# ControlVoltage.net
KiCad netlist of a schematic drawn in Altium Designer
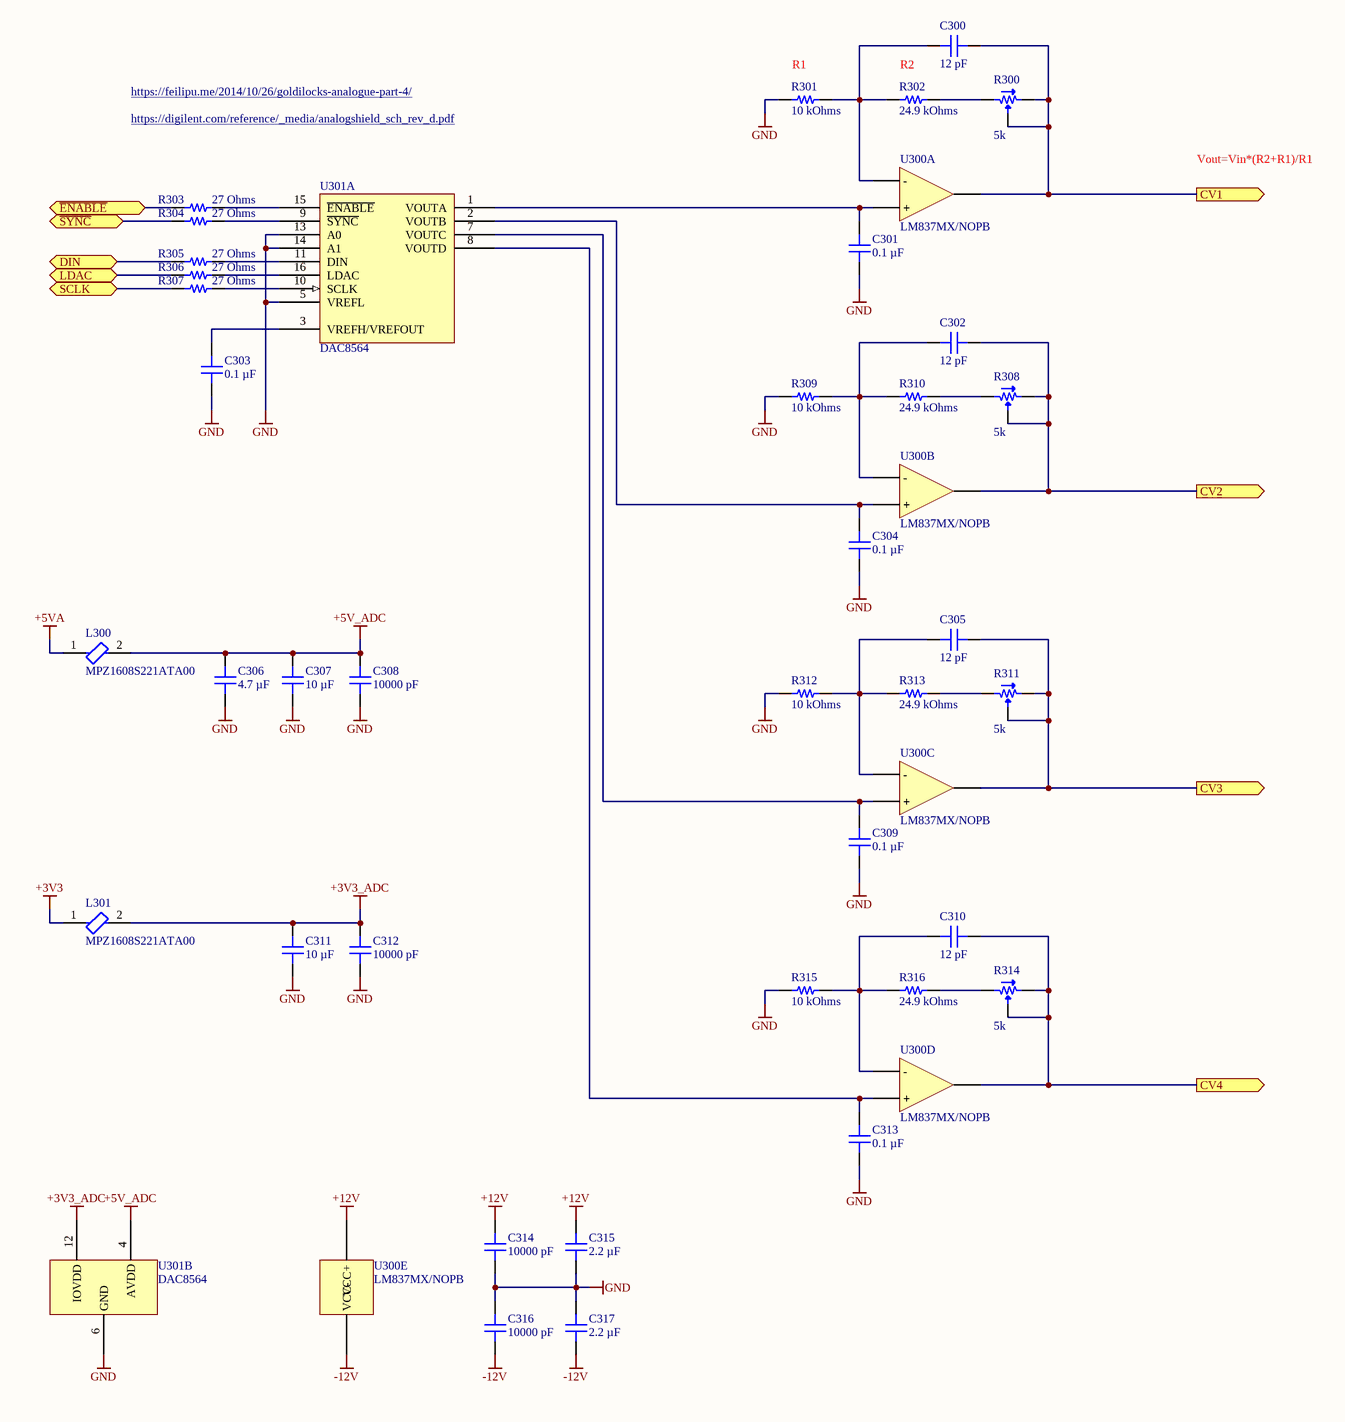
[diagram p0: ControlVoltage.SchDoc]

(export (version "E")
  (design (tool "Eeschema 10.0.6"))
  (components
    (comp (ref "C300")
      (value "12 pF")
      (footprint "CAP 0603_1608")
      (description "CAP CER 12PF 50V C0G/NPO 0603")
      (fields (field (name "PART NUMBER") "CC0603KRNPO9BN120") (field (name "MANUFACTURER") "Yageo"))
      (libsource (lib "Celestial Altium Library") (part "Capacitor"))
    )
    (comp (ref "C301")
      (value "0.1 µF")
      (footprint "CAP 0603_1608")
      (description "CAP CER 0.1UF 16V X7R 0603")
      (fields (field (name "PART NUMBER") "CS0603KRX7R7BB104") (field (name "MANUFACTURER") "Yageo"))
      (libsource (lib "Celestial Altium Library") (part "Capacitor"))
    )
    (comp (ref "C302")
      (value "12 pF")
      (footprint "CAP 0603_1608")
      (description "CAP CER 12PF 50V C0G/NPO 0603")
      (fields (field (name "PART NUMBER") "CC0603KRNPO9BN120") (field (name "MANUFACTURER") "Yageo"))
      (libsource (lib "Celestial Altium Library") (part "Capacitor"))
    )
    (comp (ref "C303")
      (value "0.1 µF")
      (footprint "CAP 0603_1608")
      (description "CAP CER 0.1UF 25V Y5V 0603")
      (fields (field (name "PART NUMBER") "CC0603MRY5V8BB104") (field (name "MANUFACTURER") "Yageo"))
      (libsource (lib "Celestial Altium Library") (part "Capacitor"))
    )
    (comp (ref "C304")
      (value "0.1 µF")
      (footprint "CAP 0603_1608")
      (description "CAP CER 0.1UF 16V X7R 0603")
      (fields (field (name "PART NUMBER") "CS0603KRX7R7BB104") (field (name "MANUFACTURER") "Yageo"))
      (libsource (lib "Celestial Altium Library") (part "Capacitor"))
    )
    (comp (ref "C305")
      (value "12 pF")
      (footprint "CAP 0603_1608")
      (description "CAP CER 12PF 50V C0G/NPO 0603")
      (fields (field (name "PART NUMBER") "CC0603KRNPO9BN120") (field (name "MANUFACTURER") "Yageo"))
      (libsource (lib "Celestial Altium Library") (part "Capacitor"))
    )
    (comp (ref "C306")
      (value "4.7 µF")
      (footprint "CAP 0603_1608")
      (description "CAP CER 4.7UF 10V X5R 0603")
      (fields (field (name "PART NUMBER") "CC0603MRX5R6BB475") (field (name "MANUFACTURER") "Yageo"))
      (libsource (lib "Celestial Altium Library") (part "Capacitor"))
    )
    (comp (ref "C307")
      (value "10 µF")
      (footprint "CAP 0603_1608")
      (description "CAP CER 10UF 4V X5R 0603")
      (fields (field (name "PART NUMBER") "CC0603MRX5R4BB106") (field (name "MANUFACTURER") "Yageo"))
      (libsource (lib "Celestial Altium Library") (part "Capacitor"))
    )
    (comp (ref "C308")
      (value "10000 pF")
      (footprint "CAP 0603_1608")
      (description "CAP CER 10000PF 50V X7R 0603")
      (fields (field (name "PART NUMBER") "CC0603JRX7R9BB103") (field (name "MANUFACTURER") "Yageo"))
      (libsource (lib "Celestial Altium Library") (part "Capacitor"))
    )
    (comp (ref "C309")
      (value "0.1 µF")
      (footprint "CAP 0603_1608")
      (description "CAP CER 0.1UF 16V X7R 0603")
      (fields (field (name "PART NUMBER") "CS0603KRX7R7BB104") (field (name "MANUFACTURER") "Yageo"))
      (libsource (lib "Celestial Altium Library") (part "Capacitor"))
    )
    (comp (ref "C310")
      (value "12 pF")
      (footprint "CAP 0603_1608")
      (description "CAP CER 12PF 50V C0G/NPO 0603")
      (fields (field (name "PART NUMBER") "CC0603KRNPO9BN120") (field (name "MANUFACTURER") "Yageo"))
      (libsource (lib "Celestial Altium Library") (part "Capacitor"))
    )
    (comp (ref "C311")
      (value "10 µF")
      (footprint "CAP 0603_1608")
      (description "CAP CER 10UF 4V X5R 0603")
      (fields (field (name "PART NUMBER") "CC0603MRX5R4BB106") (field (name "MANUFACTURER") "Yageo"))
      (libsource (lib "Celestial Altium Library") (part "Capacitor"))
    )
    (comp (ref "C312")
      (value "10000 pF")
      (footprint "CAP 0603_1608")
      (description "CAP CER 10000PF 50V X7R 0603")
      (fields (field (name "PART NUMBER") "CC0603JRX7R9BB103") (field (name "MANUFACTURER") "Yageo"))
      (libsource (lib "Celestial Altium Library") (part "Capacitor"))
    )
    (comp (ref "C313")
      (value "0.1 µF")
      (footprint "CAP 0603_1608")
      (description "CAP CER 0.1UF 16V X7R 0603")
      (fields (field (name "PART NUMBER") "CS0603KRX7R7BB104") (field (name "MANUFACTURER") "Yageo"))
      (libsource (lib "Celestial Altium Library") (part "Capacitor"))
    )
    (comp (ref "C314")
      (value "10000 pF")
      (footprint "CAP 0603_1608")
      (description "CAP CER 10000PF 50V X7R 0603")
      (fields (field (name "PART NUMBER") "CC0603JRX7R9BB103") (field (name "MANUFACTURER") "Yageo"))
      (libsource (lib "Celestial Altium Library") (part "Capacitor"))
    )
    (comp (ref "C315")
      (value "2.2 µF")
      (footprint "CAP 0603_1608")
      (description "CAP CER 2.2UF 16V Y5V 0603")
      (fields (field (name "PART NUMBER") "CC0603ZRY5V7BB225") (field (name "MANUFACTURER") "Yageo"))
      (libsource (lib "Celestial Altium Library") (part "Capacitor"))
    )
    (comp (ref "C316")
      (value "10000 pF")
      (footprint "CAP 0603_1608")
      (description "CAP CER 10000PF 50V X7R 0603")
      (fields (field (name "PART NUMBER") "CC0603JRX7R9BB103") (field (name "MANUFACTURER") "Yageo"))
      (libsource (lib "Celestial Altium Library") (part "Capacitor"))
    )
    (comp (ref "C317")
      (value "2.2 µF")
      (footprint "CAP 0603_1608")
      (description "CAP CER 2.2UF 16V Y5V 0603")
      (fields (field (name "PART NUMBER") "CC0603ZRY5V7BB225") (field (name "MANUFACTURER") "Yageo"))
      (libsource (lib "Celestial Altium Library") (part "Capacitor"))
    )
    (comp (ref "L300")
      (value "MPZ1608S221ATA00")
      (footprint "FP-MPZ1608-0_8-MFG")
      (description "Power line Ferrite Bead 220Ω @ 100MHz 2.2A DCR 0.05Ω SMD 0603")
      (fields (field (name "TOLERANCE") "25%"))
      (libsource (lib "Altium Content Vault") (part "5f30dd21d616792df468990f7003faa"))
    )
    (comp (ref "L301")
      (value "MPZ1608S221ATA00")
      (footprint "FP-MPZ1608-0_8-MFG")
      (description "Power line Ferrite Bead 220Ω @ 100MHz 2.2A DCR 0.05Ω SMD 0603")
      (fields (field (name "TOLERANCE") "25%"))
      (libsource (lib "Altium Content Vault") (part "5f30dd21d616792df468990f7003faa"))
    )
    (comp (ref "R300")
      (value "5k")
      (footprint "BOURNS_TRIM_3296")
      (description "Bourns Trimmer Resistor - Through Hole - Series 3296")
      (libsource (lib "LabratsSynthLib") (part "BOURNS_TRIM_POT_3296"))
    )
    (comp (ref "R301")
      (value "10 kOhms")
      (footprint "RES 0603_1608")
      (description "RES SMD 10K OHM 1% 1/10W 0603")
      (fields (field (name "PART NUMBER") "CRCW060310K0FKTA") (field (name "MANUFACTURER") "Vishay Dale"))
      (libsource (lib "Celestial Altium Library") (part "Resistor"))
    )
    (comp (ref "R302")
      (value "24.9 kOhms")
      (footprint "RES 0603_1608")
      (description "RES 24.9K OHM 1% 1/10W 0603")
      (fields (field (name "PART NUMBER") "CRCW060324K9FKEAC") (field (name "MANUFACTURER") "Vishay Dale"))
      (libsource (lib "Celestial Altium Library") (part "Resistor"))
    )
    (comp (ref "R303")
      (value "27 Ohms")
      (footprint "RES 0603_1608")
      (description "RES SMD 27 OHM 1% 1/10W 0603")
      (fields (field (name "PART NUMBER") "CRCW060327R0FKEA") (field (name "MANUFACTURER") "Vishay Dale"))
      (libsource (lib "Celestial Altium Library") (part "Resistor"))
    )
    (comp (ref "R304")
      (value "27 Ohms")
      (footprint "RES 0603_1608")
      (description "RES SMD 27 OHM 1% 1/10W 0603")
      (fields (field (name "PART NUMBER") "CRCW060327R0FKEA") (field (name "MANUFACTURER") "Vishay Dale"))
      (libsource (lib "Celestial Altium Library") (part "Resistor"))
    )
    (comp (ref "R305")
      (value "27 Ohms")
      (footprint "RES 0603_1608")
      (description "RES SMD 27 OHM 1% 1/10W 0603")
      (fields (field (name "PART NUMBER") "CRCW060327R0FKEA") (field (name "MANUFACTURER") "Vishay Dale"))
      (libsource (lib "Celestial Altium Library") (part "Resistor"))
    )
    (comp (ref "R306")
      (value "27 Ohms")
      (footprint "RES 0603_1608")
      (description "RES SMD 27 OHM 1% 1/10W 0603")
      (fields (field (name "PART NUMBER") "CRCW060327R0FKEA") (field (name "MANUFACTURER") "Vishay Dale"))
      (libsource (lib "Celestial Altium Library") (part "Resistor"))
    )
    (comp (ref "R307")
      (value "27 Ohms")
      (footprint "RES 0603_1608")
      (description "RES SMD 27 OHM 1% 1/10W 0603")
      (fields (field (name "PART NUMBER") "CRCW060327R0FKEA") (field (name "MANUFACTURER") "Vishay Dale"))
      (libsource (lib "Celestial Altium Library") (part "Resistor"))
    )
    (comp (ref "R308")
      (value "5k")
      (footprint "BOURNS_TRIM_3296")
      (description "Bourns Trimmer Resistor - Through Hole - Series 3296")
      (libsource (lib "LabratsSynthLib") (part "BOURNS_TRIM_POT_3296"))
    )
    (comp (ref "R309")
      (value "10 kOhms")
      (footprint "RES 0603_1608")
      (description "RES SMD 10K OHM 1% 1/10W 0603")
      (fields (field (name "PART NUMBER") "CRCW060310K0FKTA") (field (name "MANUFACTURER") "Vishay Dale"))
      (libsource (lib "Celestial Altium Library") (part "Resistor"))
    )
    (comp (ref "R310")
      (value "24.9 kOhms")
      (footprint "RES 0603_1608")
      (description "RES 24.9K OHM 1% 1/10W 0603")
      (fields (field (name "PART NUMBER") "CRCW060324K9FKEAC") (field (name "MANUFACTURER") "Vishay Dale"))
      (libsource (lib "Celestial Altium Library") (part "Resistor"))
    )
    (comp (ref "R311")
      (value "5k")
      (footprint "BOURNS_TRIM_3296")
      (description "Bourns Trimmer Resistor - Through Hole - Series 3296")
      (libsource (lib "LabratsSynthLib") (part "BOURNS_TRIM_POT_3296"))
    )
    (comp (ref "R312")
      (value "10 kOhms")
      (footprint "RES 0603_1608")
      (description "RES SMD 10K OHM 1% 1/10W 0603")
      (fields (field (name "PART NUMBER") "CRCW060310K0FKTA") (field (name "MANUFACTURER") "Vishay Dale"))
      (libsource (lib "Celestial Altium Library") (part "Resistor"))
    )
    (comp (ref "R313")
      (value "24.9 kOhms")
      (footprint "RES 0603_1608")
      (description "RES 24.9K OHM 1% 1/10W 0603")
      (fields (field (name "PART NUMBER") "CRCW060324K9FKEAC") (field (name "MANUFACTURER") "Vishay Dale"))
      (libsource (lib "Celestial Altium Library") (part "Resistor"))
    )
    (comp (ref "R314")
      (value "5k")
      (footprint "BOURNS_TRIM_3296")
      (description "Bourns Trimmer Resistor - Through Hole - Series 3296")
      (libsource (lib "LabratsSynthLib") (part "BOURNS_TRIM_POT_3296"))
    )
    (comp (ref "R315")
      (value "10 kOhms")
      (footprint "RES 0603_1608")
      (description "RES SMD 10K OHM 1% 1/10W 0603")
      (fields (field (name "PART NUMBER") "CRCW060310K0FKTA") (field (name "MANUFACTURER") "Vishay Dale"))
      (libsource (lib "Celestial Altium Library") (part "Resistor"))
    )
    (comp (ref "R316")
      (value "24.9 kOhms")
      (footprint "RES 0603_1608")
      (description "RES 24.9K OHM 1% 1/10W 0603")
      (fields (field (name "PART NUMBER") "CRCW060324K9FKEAC") (field (name "MANUFACTURER") "Vishay Dale"))
      (libsource (lib "Celestial Altium Library") (part "Resistor"))
    )
    (comp (ref "U300")
      (value "LM837MX/NOPB")
      (footprint "FP-D0014A-IPC_B")
      (description "IC OPAMP GP 4 CIRCUIT 14SOIC")
      (libsource (lib "LabratsSynthLib") (part "LM837MX/NOPB"))
    )
    (comp (ref "U301")
      (value "DAC8564")
      (footprint "SOP65P640X120-16N")
      (description "Digital to Analog Converters - DAC 16B Quad Ch Ultra-Lo Glitch Vltg Output")
      (libsource (lib "LabratsSynthLib") (part "DAC8564"))
    )
  )
  (nets
    (net (code "1") (name "+3V3") (class "Default")
      (node (ref "L301") (pin "1") (pinfunction "1_1") (pintype "passive"))
    )
    (net (code "2") (name "+3V3_ADC") (class "Default")
      (node (ref "C311") (pin "2") (pinfunction "2_2") (pintype "passive"))
      (node (ref "C312") (pin "2") (pinfunction "2_2") (pintype "passive"))
      (node (ref "L301") (pin "2") (pinfunction "2_2") (pintype "passive"))
      (node (ref "U301") (pin "12") (pinfunction "IOVDD_12") (pintype "power_in"))
    )
    (net (code "3") (name "+5VA") (class "Default")
      (node (ref "L300") (pin "1") (pinfunction "1_1") (pintype "passive"))
    )
    (net (code "4") (name "+5V_ADC") (class "Default")
      (node (ref "C306") (pin "2") (pinfunction "2_2") (pintype "passive"))
      (node (ref "C307") (pin "2") (pinfunction "2_2") (pintype "passive"))
      (node (ref "C308") (pin "2") (pinfunction "2_2") (pintype "passive"))
      (node (ref "L300") (pin "2") (pinfunction "2_2") (pintype "passive"))
      (node (ref "U301") (pin "4") (pinfunction "AVDD_4") (pintype "power_in"))
    )
    (net (code "5") (name "+12V") (class "Default")
      (node (ref "C314") (pin "2") (pinfunction "2_2") (pintype "passive"))
      (node (ref "C315") (pin "2") (pinfunction "2_2") (pintype "passive"))
      (node (ref "U300") (pin "4") (pinfunction "VCC+_4") (pintype "power_in"))
    )
    (net (code "6") (name "-12V") (class "Default")
      (node (ref "C316") (pin "1") (pinfunction "1_1") (pintype "passive"))
      (node (ref "C317") (pin "1") (pinfunction "1_1") (pintype "passive"))
      (node (ref "U300") (pin "11") (pinfunction "VCC-_11") (pintype "power_in"))
    )
    (net (code "7") (name "/CV1") (class "Default")
      (node (ref "C300") (pin "2") (pinfunction "2_2") (pintype "passive"))
      (node (ref "R300") (pin "2") (pinfunction "2_2") (pintype "passive"))
      (node (ref "R300") (pin "3") (pinfunction "3_3") (pintype "passive"))
      (node (ref "U300") (pin "1") (pinfunction "Output_1") (pintype "passive"))
    )
    (net (code "8") (name "/CV2") (class "Default")
      (node (ref "C302") (pin "2") (pinfunction "2_2") (pintype "passive"))
      (node (ref "R308") (pin "2") (pinfunction "2_2") (pintype "passive"))
      (node (ref "R308") (pin "3") (pinfunction "3_3") (pintype "passive"))
      (node (ref "U300") (pin "7") (pinfunction "Output_7") (pintype "passive"))
    )
    (net (code "9") (name "/CV3") (class "Default")
      (node (ref "C305") (pin "2") (pinfunction "2_2") (pintype "passive"))
      (node (ref "R311") (pin "2") (pinfunction "2_2") (pintype "passive"))
      (node (ref "R311") (pin "3") (pinfunction "3_3") (pintype "passive"))
      (node (ref "U300") (pin "8") (pinfunction "Output_8") (pintype "passive"))
    )
    (net (code "10") (name "/CV4") (class "Default")
      (node (ref "C310") (pin "2") (pinfunction "2_2") (pintype "passive"))
      (node (ref "R314") (pin "2") (pinfunction "2_2") (pintype "passive"))
      (node (ref "R314") (pin "3") (pinfunction "3_3") (pintype "passive"))
      (node (ref "U300") (pin "14") (pinfunction "Output_14") (pintype "passive"))
    )
    (net (code "11") (name "/DIN") (class "Default")
      (node (ref "R305") (pin "1") (pinfunction "1_1") (pintype "passive"))
    )
    (net (code "12") (name "/LDAC") (class "Default")
      (node (ref "R306") (pin "1") (pinfunction "1_1") (pintype "passive"))
    )
    (net (code "13") (name "/SCLK") (class "Default")
      (node (ref "R307") (pin "1") (pinfunction "1_1") (pintype "passive"))
    )
    (net (code "14") (name "/~{ENABLE}") (class "Default")
      (node (ref "R303") (pin "1") (pinfunction "1_1") (pintype "passive"))
    )
    (net (code "15") (name "/~{SYNC}") (class "Default")
      (node (ref "R304") (pin "1") (pinfunction "1_1") (pintype "passive"))
    )
    (net (code "16") (name "GND") (class "Default")
      (node (ref "C301") (pin "1") (pinfunction "1_1") (pintype "passive"))
      (node (ref "C303") (pin "1") (pinfunction "1_1") (pintype "passive"))
      (node (ref "C304") (pin "1") (pinfunction "1_1") (pintype "passive"))
      (node (ref "C306") (pin "1") (pinfunction "1_1") (pintype "passive"))
      (node (ref "C307") (pin "1") (pinfunction "1_1") (pintype "passive"))
      (node (ref "C308") (pin "1") (pinfunction "1_1") (pintype "passive"))
      (node (ref "C309") (pin "1") (pinfunction "1_1") (pintype "passive"))
      (node (ref "C311") (pin "1") (pinfunction "1_1") (pintype "passive"))
      (node (ref "C312") (pin "1") (pinfunction "1_1") (pintype "passive"))
      (node (ref "C313") (pin "1") (pinfunction "1_1") (pintype "passive"))
      (node (ref "C314") (pin "1") (pinfunction "1_1") (pintype "passive"))
      (node (ref "C315") (pin "1") (pinfunction "1_1") (pintype "passive"))
      (node (ref "C316") (pin "2") (pinfunction "2_2") (pintype "passive"))
      (node (ref "C317") (pin "2") (pinfunction "2_2") (pintype "passive"))
      (node (ref "R301") (pin "1") (pinfunction "1_1") (pintype "passive"))
      (node (ref "R309") (pin "1") (pinfunction "1_1") (pintype "passive"))
      (node (ref "R312") (pin "1") (pinfunction "1_1") (pintype "passive"))
      (node (ref "R315") (pin "1") (pinfunction "1_1") (pintype "passive"))
      (node (ref "U301") (pin "13") (pinfunction "A0_13") (pintype "passive"))
      (node (ref "U301") (pin "14") (pinfunction "A1_14") (pintype "passive"))
      (node (ref "U301") (pin "5") (pinfunction "VREFL_5") (pintype "passive"))
      (node (ref "U301") (pin "6") (pinfunction "GND_6") (pintype "power_in"))
    )
    (net (code "17") (name "Net-(R300-Pad1)") (class "Default")
      (node (ref "R300") (pin "1") (pinfunction "1_1") (pintype "passive"))
      (node (ref "R302") (pin "2") (pinfunction "2_2") (pintype "passive"))
    )
    (net (code "18") (name "Net-(R308-Pad1)") (class "Default")
      (node (ref "R308") (pin "1") (pinfunction "1_1") (pintype "passive"))
      (node (ref "R310") (pin "2") (pinfunction "2_2") (pintype "passive"))
    )
    (net (code "19") (name "Net-(R311-Pad1)") (class "Default")
      (node (ref "R311") (pin "1") (pinfunction "1_1") (pintype "passive"))
      (node (ref "R313") (pin "2") (pinfunction "2_2") (pintype "passive"))
    )
    (net (code "20") (name "Net-(R314-Pad1)") (class "Default")
      (node (ref "R314") (pin "1") (pinfunction "1_1") (pintype "passive"))
      (node (ref "R316") (pin "2") (pinfunction "2_2") (pintype "passive"))
    )
    (net (code "21") (name "Net-(U300A-+)") (class "Default")
      (node (ref "C301") (pin "2") (pinfunction "2_2") (pintype "passive"))
      (node (ref "U300") (pin "3") (pinfunction "+_3") (pintype "passive"))
      (node (ref "U301") (pin "1") (pinfunction "VOUTA_1") (pintype "passive"))
    )
    (net (code "22") (name "Net-(U300A--)") (class "Default")
      (node (ref "C300") (pin "1") (pinfunction "1_1") (pintype "passive"))
      (node (ref "R301") (pin "2") (pinfunction "2_2") (pintype "passive"))
      (node (ref "R302") (pin "1") (pinfunction "1_1") (pintype "passive"))
      (node (ref "U300") (pin "2") (pinfunction "-_2") (pintype "passive"))
    )
    (net (code "23") (name "Net-(U300B-+)") (class "Default")
      (node (ref "C304") (pin "2") (pinfunction "2_2") (pintype "passive"))
      (node (ref "U300") (pin "5") (pinfunction "+_5") (pintype "passive"))
      (node (ref "U301") (pin "2") (pinfunction "VOUTB_2") (pintype "passive"))
    )
    (net (code "24") (name "Net-(U300B--)") (class "Default")
      (node (ref "C302") (pin "1") (pinfunction "1_1") (pintype "passive"))
      (node (ref "R309") (pin "2") (pinfunction "2_2") (pintype "passive"))
      (node (ref "R310") (pin "1") (pinfunction "1_1") (pintype "passive"))
      (node (ref "U300") (pin "6") (pinfunction "-_6") (pintype "passive"))
    )
    (net (code "25") (name "Net-(U300C-+)") (class "Default")
      (node (ref "C309") (pin "2") (pinfunction "2_2") (pintype "passive"))
      (node (ref "U300") (pin "10") (pinfunction "+_10") (pintype "passive"))
      (node (ref "U301") (pin "7") (pinfunction "VOUTC_7") (pintype "passive"))
    )
    (net (code "26") (name "Net-(U300C--)") (class "Default")
      (node (ref "C305") (pin "1") (pinfunction "1_1") (pintype "passive"))
      (node (ref "R312") (pin "2") (pinfunction "2_2") (pintype "passive"))
      (node (ref "R313") (pin "1") (pinfunction "1_1") (pintype "passive"))
      (node (ref "U300") (pin "9") (pinfunction "-_9") (pintype "passive"))
    )
    (net (code "27") (name "Net-(U300D-+)") (class "Default")
      (node (ref "C313") (pin "2") (pinfunction "2_2") (pintype "passive"))
      (node (ref "U300") (pin "12") (pinfunction "+_12") (pintype "passive"))
      (node (ref "U301") (pin "8") (pinfunction "VOUTD_8") (pintype "passive"))
    )
    (net (code "28") (name "Net-(U300D--)") (class "Default")
      (node (ref "C310") (pin "1") (pinfunction "1_1") (pintype "passive"))
      (node (ref "R315") (pin "2") (pinfunction "2_2") (pintype "passive"))
      (node (ref "R316") (pin "1") (pinfunction "1_1") (pintype "passive"))
      (node (ref "U300") (pin "13") (pinfunction "-_13") (pintype "passive"))
    )
    (net (code "29") (name "Net-(U301A-DIN)") (class "Default")
      (node (ref "R305") (pin "2") (pinfunction "2_2") (pintype "passive"))
      (node (ref "U301") (pin "11") (pinfunction "DIN_11") (pintype "passive"))
    )
    (net (code "30") (name "Net-(U301A-LDAC)") (class "Default")
      (node (ref "R306") (pin "2") (pinfunction "2_2") (pintype "passive"))
      (node (ref "U301") (pin "16") (pinfunction "LDAC_16") (pintype "passive"))
    )
    (net (code "31") (name "Net-(U301A-SCLK)") (class "Default")
      (node (ref "R307") (pin "2") (pinfunction "2_2") (pintype "passive"))
      (node (ref "U301") (pin "10") (pinfunction "SCLK_10") (pintype "input"))
    )
    (net (code "32") (name "Net-(U301A-VREFH{slash}VREFOUT)") (class "Default")
      (node (ref "C303") (pin "2") (pinfunction "2_2") (pintype "passive"))
      (node (ref "U301") (pin "3") (pinfunction "VREFH/VREFOUT_3") (pintype "passive"))
    )
    (net (code "33") (name "Net-(U301A-~{ENABLE})") (class "Default")
      (node (ref "R303") (pin "2") (pinfunction "2_2") (pintype "passive"))
      (node (ref "U301") (pin "15") (pinfunction "~{ENABLE}_15") (pintype "passive"))
    )
    (net (code "34") (name "Net-(U301A-~{SYNC})") (class "Default")
      (node (ref "R304") (pin "2") (pinfunction "2_2") (pintype "passive"))
      (node (ref "U301") (pin "9") (pinfunction "~{SYNC}_9") (pintype "passive"))
    )
  )
)
